# eco-pulser.net
KiCad netlist of a schematic drawn in EAGLE
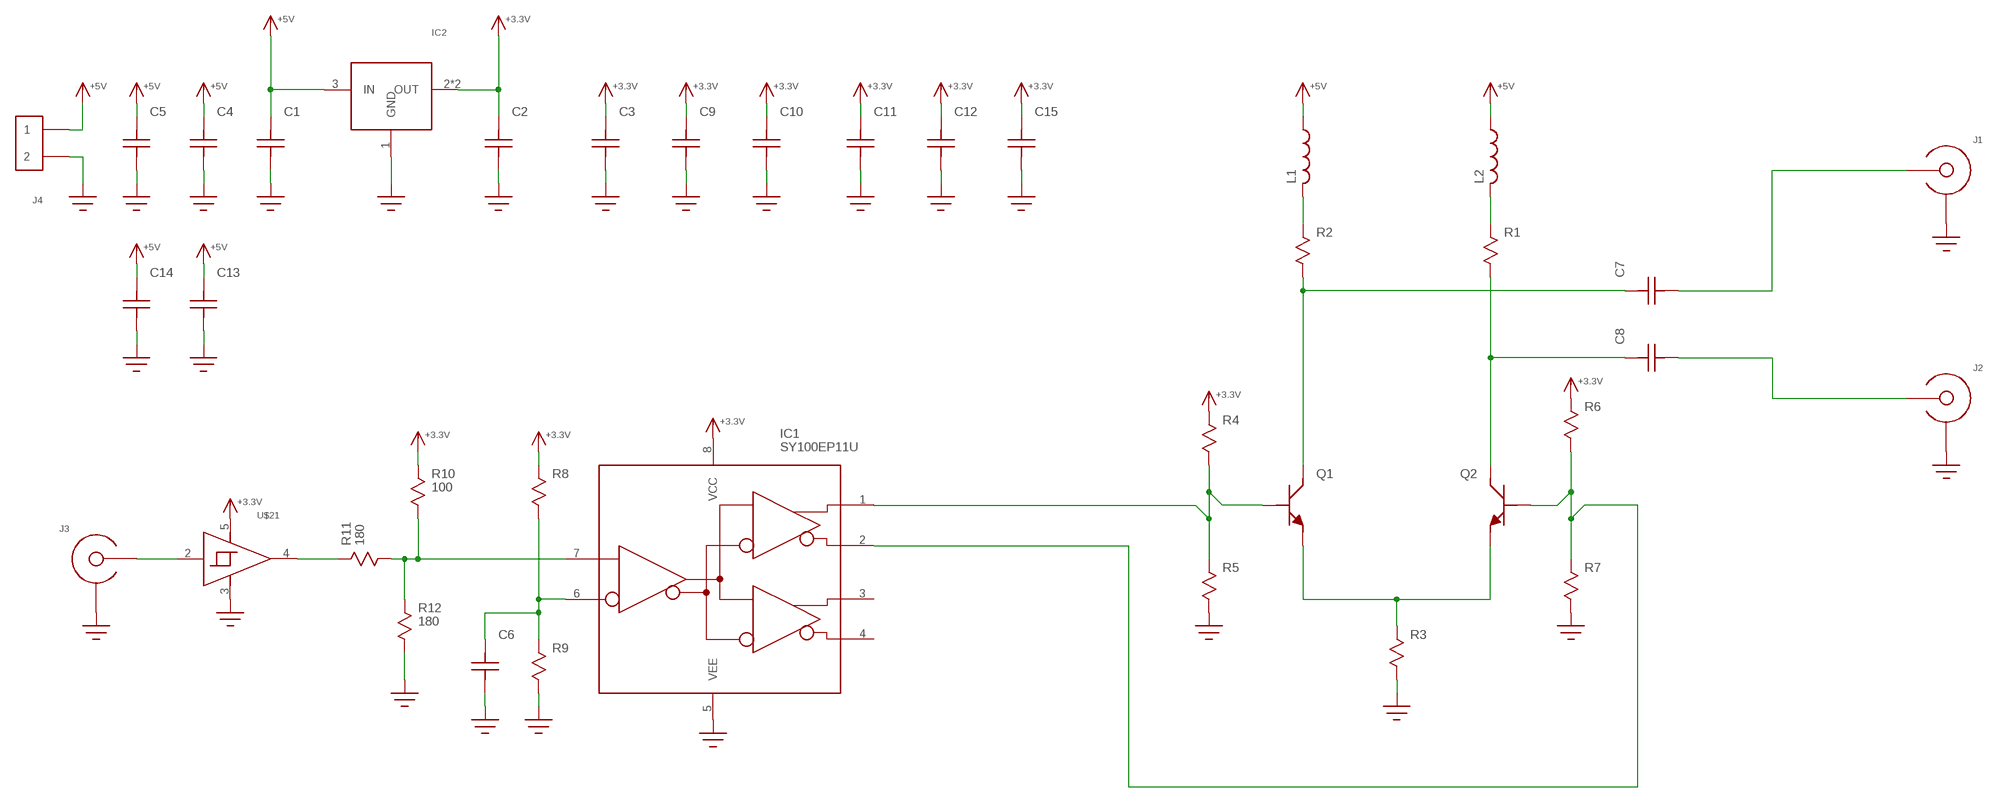
[diagram p0: schematic, sheet 1]

(export (version "E")
  (design (tool "Eeschema 10.0.6"))
  (components
    (comp (ref "C1")
      (value "C1206")
      (footprint "eagle-import:1206")
      (libsource (lib "eagle-import") (part "C1206"))
    )
    (comp (ref "C2")
      (value "C1206")
      (footprint "eagle-import:1206")
      (libsource (lib "eagle-import") (part "C1206"))
    )
    (comp (ref "C3")
      (value "C0603")
      (footprint "eagle-import:C0603")
      (libsource (lib "eagle-import") (part "C0603"))
    )
    (comp (ref "C4")
      (value "C0603")
      (footprint "eagle-import:C0603")
      (libsource (lib "eagle-import") (part "C0603"))
    )
    (comp (ref "C5")
      (value "C0603")
      (footprint "eagle-import:C0603")
      (libsource (lib "eagle-import") (part "C0603"))
    )
    (comp (ref "C6")
      (value "C0603")
      (footprint "eagle-import:C0603")
      (libsource (lib "eagle-import") (part "C0603"))
    )
    (comp (ref "C7")
      (value "C0603")
      (footprint "eagle-import:C0603")
      (libsource (lib "eagle-import") (part "C0603"))
    )
    (comp (ref "C8")
      (value "C0603")
      (footprint "eagle-import:C0603")
      (libsource (lib "eagle-import") (part "C0603"))
    )
    (comp (ref "C9")
      (value "C0603")
      (footprint "eagle-import:C0603")
      (libsource (lib "eagle-import") (part "C0603"))
    )
    (comp (ref "C10")
      (value "C0603")
      (footprint "eagle-import:C0603")
      (libsource (lib "eagle-import") (part "C0603"))
    )
    (comp (ref "C11")
      (value "C0603")
      (footprint "eagle-import:C0603")
      (libsource (lib "eagle-import") (part "C0603"))
    )
    (comp (ref "C12")
      (value "C0603")
      (footprint "eagle-import:C0603")
      (libsource (lib "eagle-import") (part "C0603"))
    )
    (comp (ref "C13")
      (value "C0603")
      (footprint "eagle-import:C0603")
      (libsource (lib "eagle-import") (part "C0603"))
    )
    (comp (ref "C14")
      (value "C0603")
      (footprint "eagle-import:C0603")
      (libsource (lib "eagle-import") (part "C0603"))
    )
    (comp (ref "C15")
      (value "C0603")
      (footprint "eagle-import:C0603")
      (libsource (lib "eagle-import") (part "C0603"))
    )
    (comp (ref "IC1")
      (value "SY100EP11U")
      (footprint "eagle-import:SOIC8")
      (libsource (lib "eagle-import") (part "SY10EP11U"))
    )
    (comp (ref "IC2")
      (value "AZ1117E")
      (footprint "eagle-import:SOT-223")
      (libsource (lib "eagle-import") (part "AZ1117E"))
    )
    (comp (ref "J1")
      (value "SMA_END_LAUNCH4L")
      (footprint "eagle-import:SMA_EDGE_LAUNCH")
      (libsource (lib "eagle-import") (part "SMA_END_LAUNCH4L"))
    )
    (comp (ref "J2")
      (value "SMA_END_LAUNCH4L")
      (footprint "eagle-import:SMA_EDGE_LAUNCH")
      (libsource (lib "eagle-import") (part "SMA_END_LAUNCH4L"))
    )
    (comp (ref "J3")
      (value "SMA_END_LAUNCH4L")
      (footprint "eagle-import:SMA_EDGE_LAUNCH")
      (libsource (lib "eagle-import") (part "SMA_END_LAUNCH4L"))
    )
    (comp (ref "J4")
      (value "HEADER_2PIN")
      (footprint "eagle-import:HEADER_2PIN")
      (libsource (lib "eagle-import") (part "HEADER_2PIN"))
    )
    (comp (ref "L1")
      (value "INDUCTOR")
      (footprint "eagle-import:R0603")
      (libsource (lib "eagle-import") (part "INDUCTOR"))
    )
    (comp (ref "L2")
      (value "INDUCTOR")
      (footprint "eagle-import:R0603")
      (libsource (lib "eagle-import") (part "INDUCTOR"))
    )
    (comp (ref "Q1")
      (value "NPN-BFP740")
      (footprint "eagle-import:SOT343")
      (libsource (lib "eagle-import") (part "NPN-BFP740"))
    )
    (comp (ref "Q2")
      (value "NPN-BFP740")
      (footprint "eagle-import:SOT343")
      (libsource (lib "eagle-import") (part "NPN-BFP740"))
    )
    (comp (ref "R1")
      (value "R0603")
      (footprint "eagle-import:R0603")
      (libsource (lib "eagle-import") (part "R0603"))
    )
    (comp (ref "R2")
      (value "R0603")
      (footprint "eagle-import:R0603")
      (libsource (lib "eagle-import") (part "R0603"))
    )
    (comp (ref "R3")
      (value "R0603")
      (footprint "eagle-import:R0603")
      (libsource (lib "eagle-import") (part "R0603"))
    )
    (comp (ref "R4")
      (value "R0603")
      (footprint "eagle-import:R0603")
      (libsource (lib "eagle-import") (part "R0603"))
    )
    (comp (ref "R5")
      (value "R0603")
      (footprint "eagle-import:R0603")
      (libsource (lib "eagle-import") (part "R0603"))
    )
    (comp (ref "R6")
      (value "R0603")
      (footprint "eagle-import:R0603")
      (libsource (lib "eagle-import") (part "R0603"))
    )
    (comp (ref "R7")
      (value "R0603")
      (footprint "eagle-import:R0603")
      (libsource (lib "eagle-import") (part "R0603"))
    )
    (comp (ref "R8")
      (value "R0603")
      (footprint "eagle-import:R0603")
      (libsource (lib "eagle-import") (part "R0603"))
    )
    (comp (ref "R9")
      (value "R0603")
      (footprint "eagle-import:R0603")
      (libsource (lib "eagle-import") (part "R0603"))
    )
    (comp (ref "R10")
      (value "100")
      (footprint "eagle-import:R0603")
      (libsource (lib "eagle-import") (part "R0603"))
    )
    (comp (ref "R11")
      (value "180")
      (footprint "eagle-import:R0603")
      (libsource (lib "eagle-import") (part "R0603"))
    )
    (comp (ref "R12")
      (value "180")
      (footprint "eagle-import:R0603")
      (libsource (lib "eagle-import") (part "R0603"))
    )
    (comp (ref "U$21")
      (value "74LVC1G17")
      (footprint "eagle-import:SOT23-5")
      (libsource (lib "eagle-import") (part "74LVC1G17"))
    )
  )
  (nets
    (net (code "1") (name "+3.3V") (class "Default")
      (node (ref "C10") (pin "P$2") (pinfunction "P$2_P$2") (pintype "bidirectional"))
      (node (ref "C11") (pin "P$2") (pinfunction "P$2_P$2") (pintype "bidirectional"))
      (node (ref "C12") (pin "P$2") (pinfunction "P$2_P$2") (pintype "bidirectional"))
      (node (ref "C15") (pin "P$2") (pinfunction "P$2_P$2") (pintype "bidirectional"))
      (node (ref "C2") (pin "P$2") (pinfunction "P$2_P$2") (pintype "bidirectional"))
      (node (ref "C3") (pin "P$2") (pinfunction "P$2_P$2") (pintype "bidirectional"))
      (node (ref "C9") (pin "P$2") (pinfunction "P$2_P$2") (pintype "bidirectional"))
      (node (ref "IC1") (pin "8") (pinfunction "VCC_8") (pintype "bidirectional"))
      (node (ref "IC2") (pin "2") (pinfunction "OUT_2") (pintype "bidirectional"))
      (node (ref "IC2") (pin "4") (pinfunction "OUT_4") (pintype "bidirectional"))
      (node (ref "R10") (pin "P$1") (pinfunction "P$3_P$1") (pintype "bidirectional"))
      (node (ref "R4") (pin "P$1") (pinfunction "P$3_P$1") (pintype "bidirectional"))
      (node (ref "R6") (pin "P$1") (pinfunction "P$3_P$1") (pintype "bidirectional"))
      (node (ref "R8") (pin "P$1") (pinfunction "P$3_P$1") (pintype "bidirectional"))
      (node (ref "U$21") (pin "5") (pinfunction "VCC_5") (pintype "bidirectional"))
    )
    (net (code "2") (name "+5V") (class "Default")
      (node (ref "C1") (pin "P$2") (pinfunction "P$2_P$2") (pintype "bidirectional"))
      (node (ref "C13") (pin "P$2") (pinfunction "P$2_P$2") (pintype "bidirectional"))
      (node (ref "C14") (pin "P$2") (pinfunction "P$2_P$2") (pintype "bidirectional"))
      (node (ref "C4") (pin "P$2") (pinfunction "P$2_P$2") (pintype "bidirectional"))
      (node (ref "C5") (pin "P$2") (pinfunction "P$2_P$2") (pintype "bidirectional"))
      (node (ref "IC2") (pin "3") (pinfunction "IN_3") (pintype "bidirectional"))
      (node (ref "J4") (pin "1") (pinfunction "1_1") (pintype "bidirectional"))
      (node (ref "L1") (pin "P$1") (pinfunction "1_P$1") (pintype "passive"))
      (node (ref "L2") (pin "P$1") (pinfunction "1_P$1") (pintype "passive"))
    )
    (net (code "3") (name "GND") (class "Default")
      (node (ref "C1") (pin "P$1") (pinfunction "P$1_P$1") (pintype "bidirectional"))
      (node (ref "C10") (pin "P$1") (pinfunction "P$1_P$1") (pintype "bidirectional"))
      (node (ref "C11") (pin "P$1") (pinfunction "P$1_P$1") (pintype "bidirectional"))
      (node (ref "C12") (pin "P$1") (pinfunction "P$1_P$1") (pintype "bidirectional"))
      (node (ref "C13") (pin "P$1") (pinfunction "P$1_P$1") (pintype "bidirectional"))
      (node (ref "C14") (pin "P$1") (pinfunction "P$1_P$1") (pintype "bidirectional"))
      (node (ref "C15") (pin "P$1") (pinfunction "P$1_P$1") (pintype "bidirectional"))
      (node (ref "C2") (pin "P$1") (pinfunction "P$1_P$1") (pintype "bidirectional"))
      (node (ref "C3") (pin "P$1") (pinfunction "P$1_P$1") (pintype "bidirectional"))
      (node (ref "C4") (pin "P$1") (pinfunction "P$1_P$1") (pintype "bidirectional"))
      (node (ref "C5") (pin "P$1") (pinfunction "P$1_P$1") (pintype "bidirectional"))
      (node (ref "C6") (pin "P$1") (pinfunction "P$1_P$1") (pintype "bidirectional"))
      (node (ref "C9") (pin "P$1") (pinfunction "P$1_P$1") (pintype "bidirectional"))
      (node (ref "IC1") (pin "5") (pinfunction "VEE_5") (pintype "bidirectional"))
      (node (ref "IC2") (pin "1") (pinfunction "GND_1") (pintype "bidirectional"))
      (node (ref "J1") (pin "BOTTOM_PAD") (pinfunction "SHIELD_BOTTOM_PAD") (pintype "bidirectional"))
      (node (ref "J1") (pin "GND@1") (pinfunction "SHIELD_GND@1") (pintype "bidirectional"))
      (node (ref "J1") (pin "GND@14") (pinfunction "SHIELD_GND@14") (pintype "bidirectional"))
      (node (ref "J1") (pin "GND@15") (pinfunction "SHIELD_GND@15") (pintype "bidirectional"))
      (node (ref "J1") (pin "GND@16") (pinfunction "SHIELD_GND@16") (pintype "bidirectional"))
      (node (ref "J1") (pin "GND@17") (pinfunction "SHIELD_GND@17") (pintype "bidirectional"))
      (node (ref "J1") (pin "GND@2") (pinfunction "SHIELD_GND@2") (pintype "bidirectional"))
      (node (ref "J1") (pin "GND@3") (pinfunction "SHIELD_GND@3") (pintype "bidirectional"))
      (node (ref "J1") (pin "GND@4") (pinfunction "SHIELD_GND@4") (pintype "bidirectional"))
      (node (ref "J1") (pin "GND@5") (pinfunction "SHIELD_GND@5") (pintype "bidirectional"))
      (node (ref "J1") (pin "GND@6") (pinfunction "SHIELD_GND@6") (pintype "bidirectional"))
      (node (ref "J1") (pin "GND@7") (pinfunction "SHIELD_GND@7") (pintype "bidirectional"))
      (node (ref "J1") (pin "GND@8") (pinfunction "SHIELD_GND@8") (pintype "bidirectional"))
      (node (ref "J1") (pin "GND_PAD1") (pinfunction "SHIELD_GND_PAD1") (pintype "bidirectional"))
      (node (ref "J1") (pin "GND_PAD2") (pinfunction "SHIELD_GND_PAD2") (pintype "bidirectional"))
      (node (ref "J2") (pin "BOTTOM_PAD") (pinfunction "SHIELD_BOTTOM_PAD") (pintype "bidirectional"))
      (node (ref "J2") (pin "GND@1") (pinfunction "SHIELD_GND@1") (pintype "bidirectional"))
      (node (ref "J2") (pin "GND@14") (pinfunction "SHIELD_GND@14") (pintype "bidirectional"))
      (node (ref "J2") (pin "GND@15") (pinfunction "SHIELD_GND@15") (pintype "bidirectional"))
      (node (ref "J2") (pin "GND@16") (pinfunction "SHIELD_GND@16") (pintype "bidirectional"))
      (node (ref "J2") (pin "GND@17") (pinfunction "SHIELD_GND@17") (pintype "bidirectional"))
      (node (ref "J2") (pin "GND@2") (pinfunction "SHIELD_GND@2") (pintype "bidirectional"))
      (node (ref "J2") (pin "GND@3") (pinfunction "SHIELD_GND@3") (pintype "bidirectional"))
      (node (ref "J2") (pin "GND@4") (pinfunction "SHIELD_GND@4") (pintype "bidirectional"))
      (node (ref "J2") (pin "GND@5") (pinfunction "SHIELD_GND@5") (pintype "bidirectional"))
      (node (ref "J2") (pin "GND@6") (pinfunction "SHIELD_GND@6") (pintype "bidirectional"))
      (node (ref "J2") (pin "GND@7") (pinfunction "SHIELD_GND@7") (pintype "bidirectional"))
      (node (ref "J2") (pin "GND@8") (pinfunction "SHIELD_GND@8") (pintype "bidirectional"))
      (node (ref "J2") (pin "GND_PAD1") (pinfunction "SHIELD_GND_PAD1") (pintype "bidirectional"))
      (node (ref "J2") (pin "GND_PAD2") (pinfunction "SHIELD_GND_PAD2") (pintype "bidirectional"))
      (node (ref "J3") (pin "BOTTOM_PAD") (pinfunction "SHIELD_BOTTOM_PAD") (pintype "bidirectional"))
      (node (ref "J3") (pin "GND@1") (pinfunction "SHIELD_GND@1") (pintype "bidirectional"))
      (node (ref "J3") (pin "GND@14") (pinfunction "SHIELD_GND@14") (pintype "bidirectional"))
      (node (ref "J3") (pin "GND@15") (pinfunction "SHIELD_GND@15") (pintype "bidirectional"))
      (node (ref "J3") (pin "GND@16") (pinfunction "SHIELD_GND@16") (pintype "bidirectional"))
      (node (ref "J3") (pin "GND@17") (pinfunction "SHIELD_GND@17") (pintype "bidirectional"))
      (node (ref "J3") (pin "GND@2") (pinfunction "SHIELD_GND@2") (pintype "bidirectional"))
      (node (ref "J3") (pin "GND@3") (pinfunction "SHIELD_GND@3") (pintype "bidirectional"))
      (node (ref "J3") (pin "GND@4") (pinfunction "SHIELD_GND@4") (pintype "bidirectional"))
      (node (ref "J3") (pin "GND@5") (pinfunction "SHIELD_GND@5") (pintype "bidirectional"))
      (node (ref "J3") (pin "GND@6") (pinfunction "SHIELD_GND@6") (pintype "bidirectional"))
      (node (ref "J3") (pin "GND@7") (pinfunction "SHIELD_GND@7") (pintype "bidirectional"))
      (node (ref "J3") (pin "GND@8") (pinfunction "SHIELD_GND@8") (pintype "bidirectional"))
      (node (ref "J3") (pin "GND_PAD1") (pinfunction "SHIELD_GND_PAD1") (pintype "bidirectional"))
      (node (ref "J3") (pin "GND_PAD2") (pinfunction "SHIELD_GND_PAD2") (pintype "bidirectional"))
      (node (ref "J4") (pin "2") (pinfunction "2_2") (pintype "bidirectional"))
      (node (ref "R12") (pin "P$2") (pinfunction "P$4_P$2") (pintype "bidirectional"))
      (node (ref "R3") (pin "P$2") (pinfunction "P$4_P$2") (pintype "bidirectional"))
      (node (ref "R5") (pin "P$2") (pinfunction "P$4_P$2") (pintype "bidirectional"))
      (node (ref "R7") (pin "P$2") (pinfunction "P$4_P$2") (pintype "bidirectional"))
      (node (ref "R9") (pin "P$2") (pinfunction "P$4_P$2") (pintype "bidirectional"))
      (node (ref "U$21") (pin "3") (pinfunction "GND_3") (pintype "bidirectional"))
    )
    (net (code "4") (name "Net-(C7-PadP$1)") (class "Default")
      (node (ref "C7") (pin "P$1") (pinfunction "P$1_P$1") (pintype "bidirectional"))
      (node (ref "J1") (pin "CENTER@1") (pinfunction "CENTER_CENTER@1") (pintype "bidirectional"))
      (node (ref "J1") (pin "CENTER@2") (pinfunction "CENTER_CENTER@2") (pintype "bidirectional"))
    )
    (net (code "5") (name "Net-(C8-PadP$1)") (class "Default")
      (node (ref "C8") (pin "P$1") (pinfunction "P$1_P$1") (pintype "bidirectional"))
      (node (ref "J2") (pin "CENTER@1") (pinfunction "CENTER_CENTER@1") (pintype "bidirectional"))
      (node (ref "J2") (pin "CENTER@2") (pinfunction "CENTER_CENTER@2") (pintype "bidirectional"))
    )
    (net (code "6") (name "Net-(IC1-D)") (class "Default")
      (node (ref "IC1") (pin "7") (pinfunction "D_7") (pintype "bidirectional"))
      (node (ref "R10") (pin "P$2") (pinfunction "P$4_P$2") (pintype "bidirectional"))
      (node (ref "R11") (pin "P$2") (pinfunction "P$4_P$2") (pintype "bidirectional"))
      (node (ref "R12") (pin "P$1") (pinfunction "P$3_P$1") (pintype "bidirectional"))
    )
    (net (code "7") (name "Net-(IC1-Q0)") (class "Default")
      (node (ref "IC1") (pin "1") (pinfunction "Q0_1") (pintype "bidirectional"))
      (node (ref "Q1") (pin "1") (pinfunction "B_1") (pintype "bidirectional"))
      (node (ref "R4") (pin "P$2") (pinfunction "P$4_P$2") (pintype "bidirectional"))
      (node (ref "R5") (pin "P$1") (pinfunction "P$3_P$1") (pintype "bidirectional"))
    )
    (net (code "8") (name "Net-(IC1-~{D})") (class "Default")
      (node (ref "C6") (pin "P$2") (pinfunction "P$2_P$2") (pintype "bidirectional"))
      (node (ref "IC1") (pin "6") (pinfunction "~{D}_6") (pintype "bidirectional"))
      (node (ref "R8") (pin "P$2") (pinfunction "P$4_P$2") (pintype "bidirectional"))
      (node (ref "R9") (pin "P$1") (pinfunction "P$3_P$1") (pintype "bidirectional"))
    )
    (net (code "9") (name "Net-(IC1-~{Q0})") (class "Default")
      (node (ref "IC1") (pin "2") (pinfunction "~{Q0}_2") (pintype "bidirectional"))
      (node (ref "Q2") (pin "1") (pinfunction "B_1") (pintype "bidirectional"))
      (node (ref "R6") (pin "P$2") (pinfunction "P$4_P$2") (pintype "bidirectional"))
      (node (ref "R7") (pin "P$1") (pinfunction "P$3_P$1") (pintype "bidirectional"))
    )
    (net (code "10") (name "Net-(L1-2)") (class "Default")
      (node (ref "L1") (pin "P$2") (pinfunction "2_P$2") (pintype "passive"))
      (node (ref "R2") (pin "P$1") (pinfunction "P$3_P$1") (pintype "bidirectional"))
    )
    (net (code "11") (name "Net-(L2-2)") (class "Default")
      (node (ref "L2") (pin "P$2") (pinfunction "2_P$2") (pintype "passive"))
      (node (ref "R1") (pin "P$1") (pinfunction "P$3_P$1") (pintype "bidirectional"))
    )
    (net (code "12") (name "Net-(Q1-C)") (class "Default")
      (node (ref "C7") (pin "P$2") (pinfunction "P$2_P$2") (pintype "bidirectional"))
      (node (ref "Q1") (pin "3") (pinfunction "C_3") (pintype "bidirectional"))
      (node (ref "R2") (pin "P$2") (pinfunction "P$4_P$2") (pintype "bidirectional"))
    )
    (net (code "13") (name "Net-(Q2-C)") (class "Default")
      (node (ref "C8") (pin "P$2") (pinfunction "P$2_P$2") (pintype "bidirectional"))
      (node (ref "Q2") (pin "3") (pinfunction "C_3") (pintype "bidirectional"))
      (node (ref "R1") (pin "P$2") (pinfunction "P$4_P$2") (pintype "bidirectional"))
    )
    (net (code "14") (name "Net-(R3-P$3)") (class "Default")
      (node (ref "Q1") (pin "2") (pinfunction "E_2") (pintype "bidirectional"))
      (node (ref "Q1") (pin "4") (pinfunction "E_4") (pintype "bidirectional"))
      (node (ref "Q2") (pin "2") (pinfunction "E_2") (pintype "bidirectional"))
      (node (ref "Q2") (pin "4") (pinfunction "E_4") (pintype "bidirectional"))
      (node (ref "R3") (pin "P$1") (pinfunction "P$3_P$1") (pintype "bidirectional"))
    )
    (net (code "15") (name "Net-(R11-P$3)") (class "Default")
      (node (ref "R11") (pin "P$1") (pinfunction "P$3_P$1") (pintype "bidirectional"))
      (node (ref "U$21") (pin "4") (pinfunction "OUT_4") (pintype "bidirectional"))
    )
    (net (code "16") (name "Net-(U$21-IN)") (class "Default")
      (node (ref "J3") (pin "CENTER@1") (pinfunction "CENTER_CENTER@1") (pintype "bidirectional"))
      (node (ref "J3") (pin "CENTER@2") (pinfunction "CENTER_CENTER@2") (pintype "bidirectional"))
      (node (ref "U$21") (pin "2") (pinfunction "IN_2") (pintype "bidirectional"))
    )
    (net (code "17") (name "unconnected-(IC1-Q1-Pad3)") (class "Default")
      (node (ref "IC1") (pin "3") (pinfunction "Q1_3") (pintype "bidirectional"))
    )
    (net (code "18") (name "unconnected-(IC1-~{Q1}-Pad4)") (class "Default")
      (node (ref "IC1") (pin "4") (pinfunction "~{Q1}_4") (pintype "bidirectional"))
    )
  )
)
